# TSOC_USBUART2_R4_0.net
KiCad netlist of a schematic drawn in EAGLE
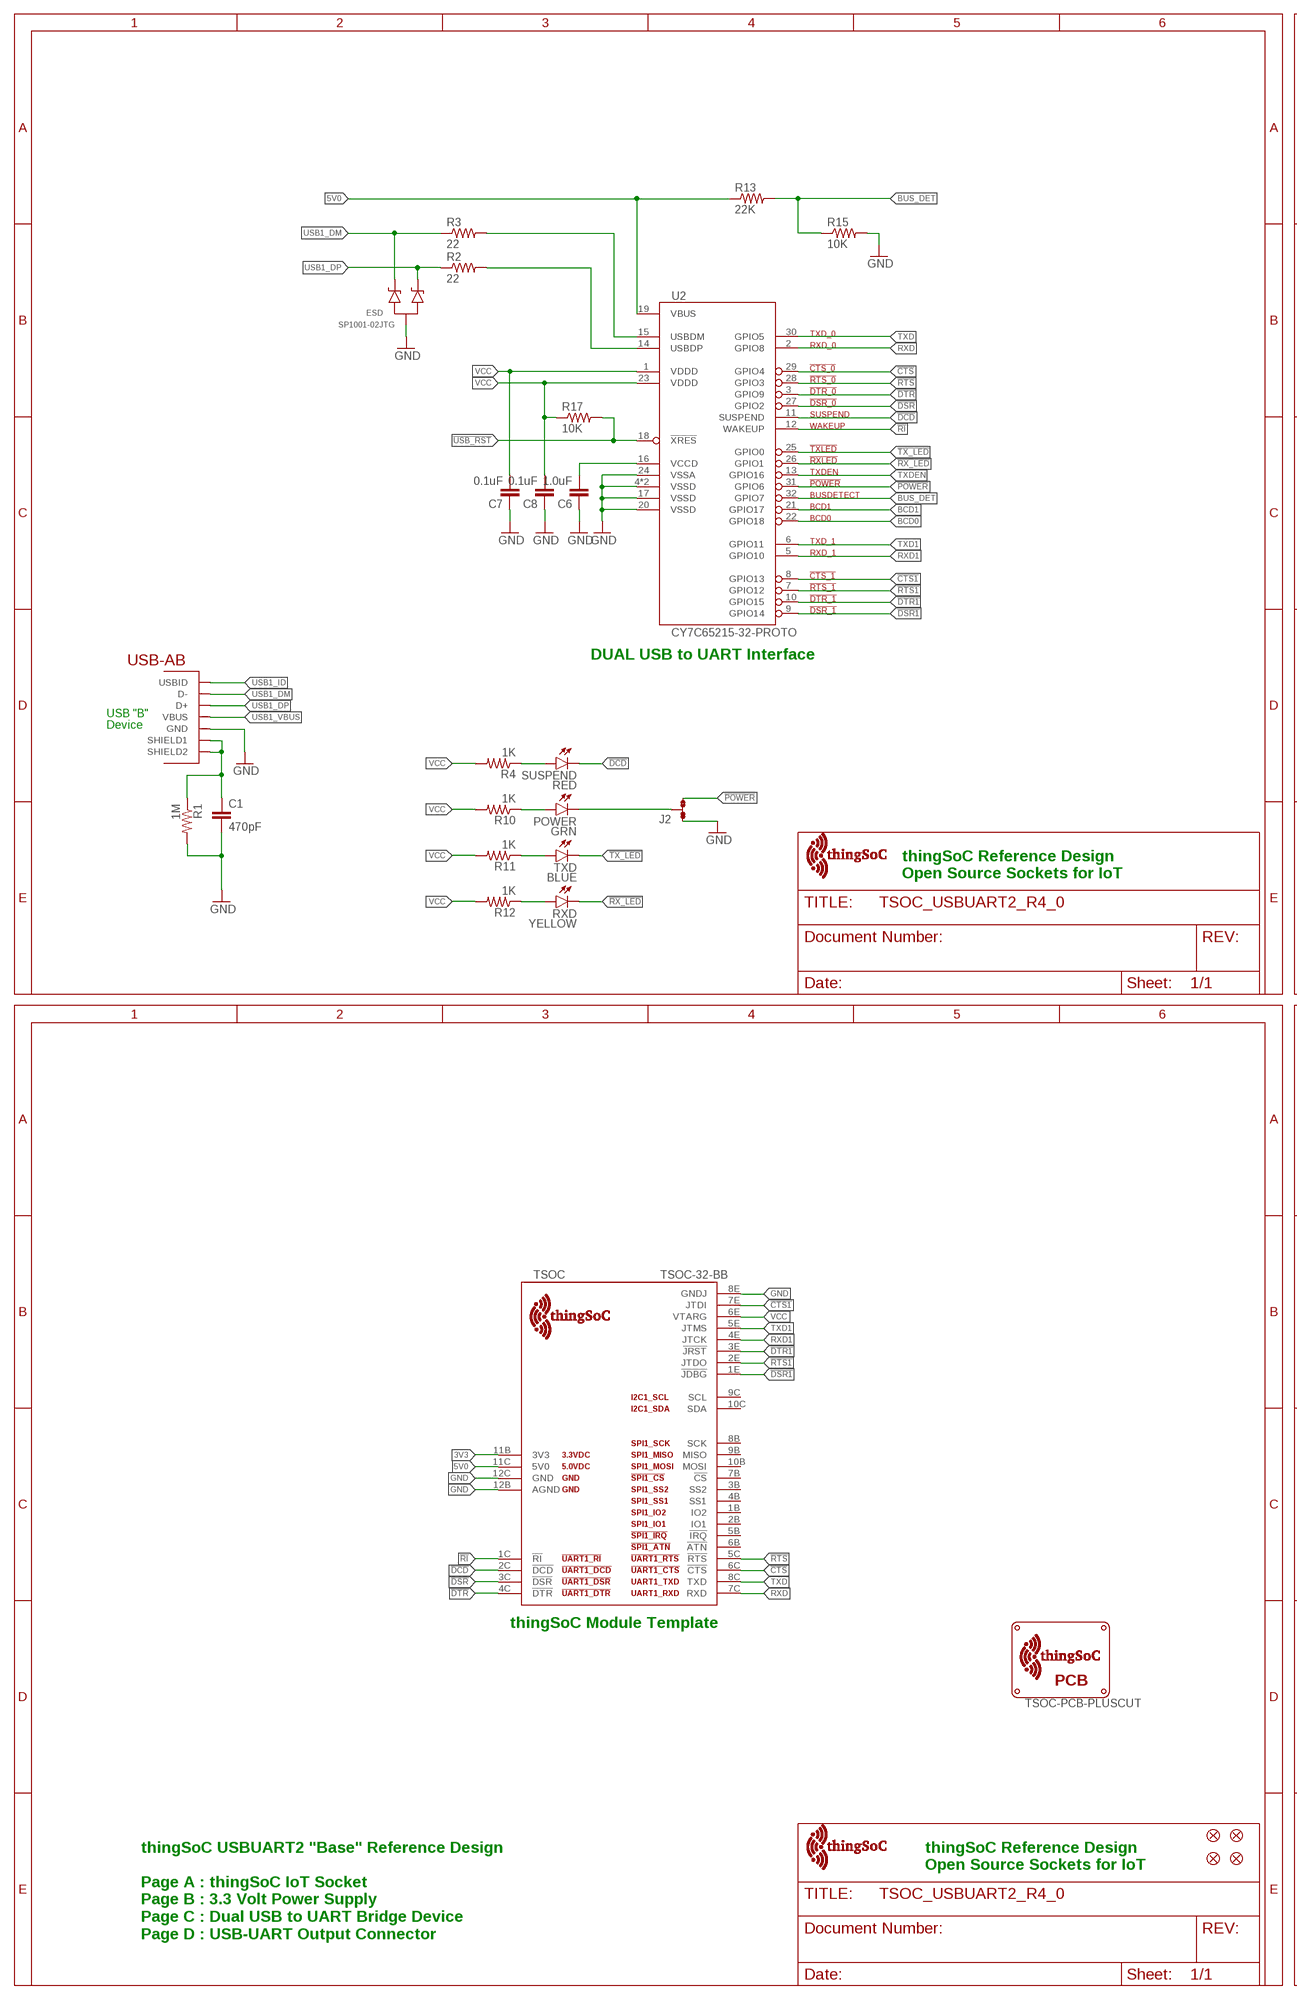
[diagram p0: schematic, sheet 1, part 1 of 2]
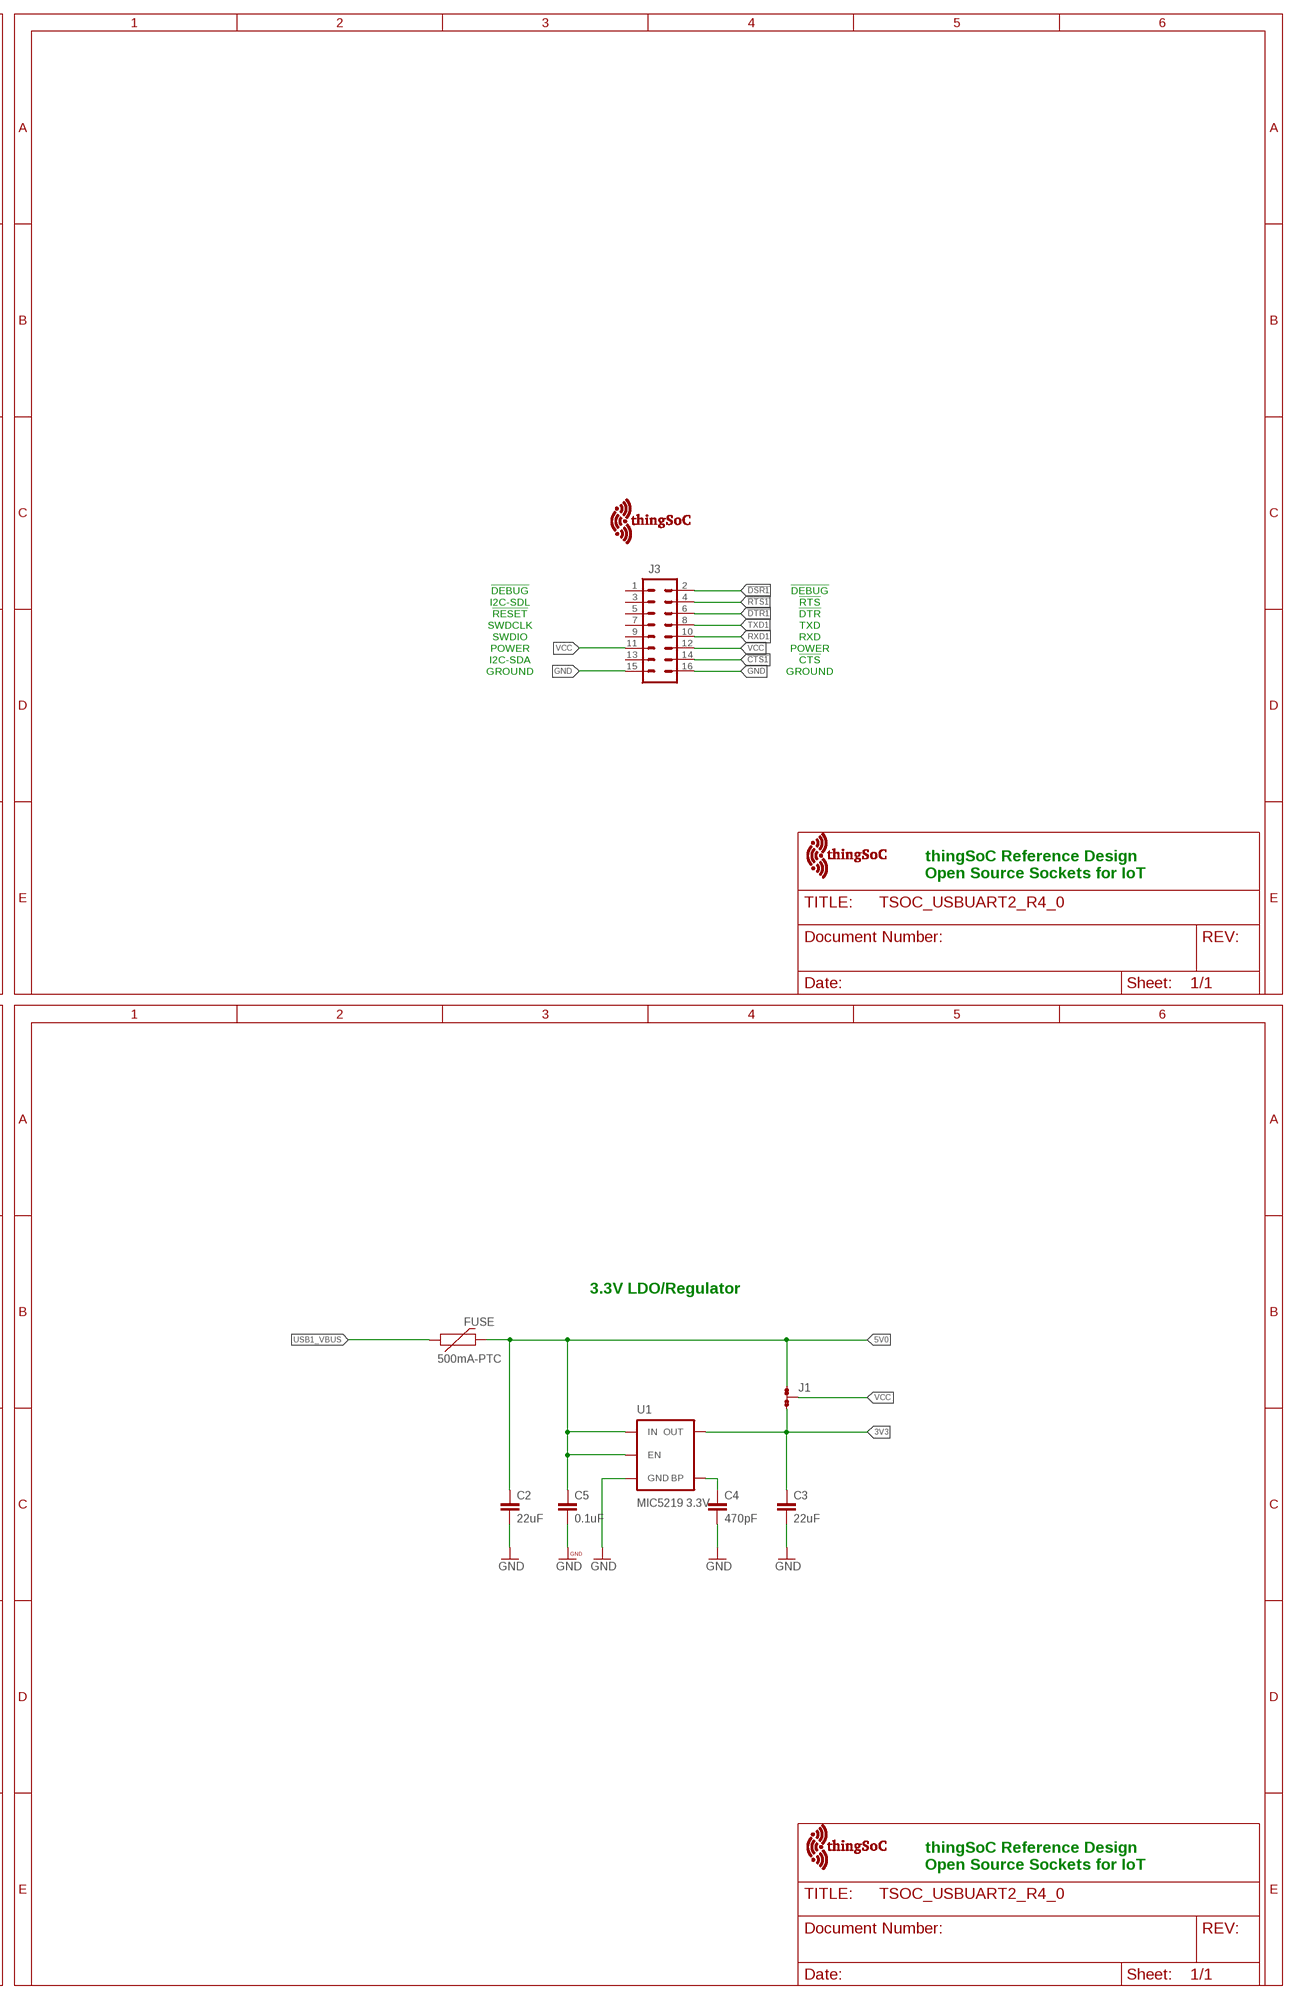
[diagram p1: schematic, sheet 1, part 2 of 2]

(export (version "E")
  (design (tool "Eeschema 10.0.6"))
  (components
    (comp (ref "C1")
      (value "470pF")
      (footprint "eagle-import:EIA-0603")
      (libsource (lib "eagle-import") (part "CAP-0603"))
    )
    (comp (ref "C2")
      (value "22uF")
      (footprint "eagle-import:EIA-1206")
      (libsource (lib "eagle-import") (part "CAP-1206"))
    )
    (comp (ref "C3")
      (value "22uF")
      (footprint "eagle-import:EIA-1206")
      (libsource (lib "eagle-import") (part "CAP-1206"))
    )
    (comp (ref "C4")
      (value "470pF")
      (footprint "eagle-import:EIA-0603")
      (libsource (lib "eagle-import") (part "CAP-0603"))
    )
    (comp (ref "C5")
      (value "0.1uF")
      (footprint "eagle-import:EIA-0603")
      (libsource (lib "eagle-import") (part "CAP-0603"))
    )
    (comp (ref "C6")
      (value "1.0uF")
      (footprint "eagle-import:EIA-0603")
      (libsource (lib "eagle-import") (part "CAP-0603"))
    )
    (comp (ref "C7")
      (value "0.1uF")
      (footprint "eagle-import:EIA-0603")
      (libsource (lib "eagle-import") (part "CAP-0603"))
    )
    (comp (ref "C8")
      (value "0.1uF")
      (footprint "eagle-import:EIA-0603")
      (libsource (lib "eagle-import") (part "CAP-0603"))
    )
    (comp (ref "ESD")
      (value "SP1001-02JTG")
      (footprint "eagle-import:SC70-3")
      (libsource (lib "eagle-import") (part "SP1001-02JTG"))
    )
    (comp (ref "FID1")
      (value "FIDUCIALUFIDUCIAL")
      (footprint "eagle-import:MICRO-FIDUCIAL")
      (libsource (lib "eagle-import") (part "FIDUCIALUFIDUCIAL"))
    )
    (comp (ref "FID2")
      (value "FIDUCIALUFIDUCIAL")
      (footprint "eagle-import:MICRO-FIDUCIAL")
      (libsource (lib "eagle-import") (part "FIDUCIALUFIDUCIAL"))
    )
    (comp (ref "FID3")
      (value "FIDUCIALUFIDUCIAL")
      (footprint "eagle-import:MICRO-FIDUCIAL")
      (libsource (lib "eagle-import") (part "FIDUCIALUFIDUCIAL"))
    )
    (comp (ref "FID4")
      (value "FIDUCIALUFIDUCIAL")
      (footprint "eagle-import:MICRO-FIDUCIAL")
      (libsource (lib "eagle-import") (part "FIDUCIALUFIDUCIAL"))
    )
    (comp (ref "FUSE")
      (value "500mA-PTC")
      (footprint "eagle-import:PTC-1206")
      (libsource (lib "eagle-import") (part "PTCSMD"))
    )
    (comp (ref "J1")
      (value "JMP-3-1_2")
      (footprint "eagle-import:JMP-3-1_2")
      (libsource (lib "eagle-import") (part "JMP-3-1_2"))
    )
    (comp (ref "J2")
      (value "JMP-3-1_2")
      (footprint "eagle-import:JMP-3-1_2")
      (libsource (lib "eagle-import") (part "JMP-3-1_2"))
    )
    (comp (ref "J3")
      (value "M08X2")
      (footprint "eagle-import:2X8")
      (libsource (lib "eagle-import") (part "M08X2"))
    )
    (comp (ref "POWER")
      (value "GRN")
      (footprint "eagle-import:LED-0603")
      (libsource (lib "eagle-import") (part "LED0603"))
    )
    (comp (ref "R1")
      (value "1M")
      (footprint "eagle-import:EIA-0603")
      (libsource (lib "eagle-import") (part "RESISTOR-0603"))
    )
    (comp (ref "R2")
      (value "22")
      (footprint "eagle-import:EIA-0603")
      (libsource (lib "eagle-import") (part "RESISTOR-0603"))
    )
    (comp (ref "R3")
      (value "22")
      (footprint "eagle-import:EIA-0603")
      (libsource (lib "eagle-import") (part "RESISTOR-0603"))
    )
    (comp (ref "R4")
      (value "1K")
      (footprint "eagle-import:EIA-0603")
      (libsource (lib "eagle-import") (part "RESISTOR-0603"))
    )
    (comp (ref "R10")
      (value "1K")
      (footprint "eagle-import:EIA-0603")
      (libsource (lib "eagle-import") (part "RESISTOR-0603"))
    )
    (comp (ref "R11")
      (value "1K")
      (footprint "eagle-import:EIA-0603")
      (libsource (lib "eagle-import") (part "RESISTOR-0603"))
    )
    (comp (ref "R12")
      (value "1K")
      (footprint "eagle-import:EIA-0603")
      (libsource (lib "eagle-import") (part "RESISTOR-0603"))
    )
    (comp (ref "R13")
      (value "22K")
      (footprint "eagle-import:EIA-0603")
      (libsource (lib "eagle-import") (part "RESISTOR-0603"))
    )
    (comp (ref "R15")
      (value "10K")
      (footprint "eagle-import:EIA-0603")
      (libsource (lib "eagle-import") (part "RESISTOR-0603"))
    )
    (comp (ref "R17")
      (value "10K")
      (footprint "eagle-import:EIA-0603")
      (libsource (lib "eagle-import") (part "RESISTOR-0603"))
    )
    (comp (ref "RXD")
      (value "YELLOW")
      (footprint "eagle-import:LED-0603")
      (libsource (lib "eagle-import") (part "LED0603"))
    )
    (comp (ref "SUSPEND")
      (value "RED")
      (footprint "eagle-import:LED-0603")
      (libsource (lib "eagle-import") (part "LED0603"))
    )
    (comp (ref "TSOC")
      (value "TSOC-32-BB")
      (footprint "eagle-import:TSOC-BB-S32")
      (libsource (lib "eagle-import") (part "TSOC-32-BB"))
    )
    (comp (ref "TXD")
      (value "BLUE")
      (footprint "eagle-import:LED-0603")
      (libsource (lib "eagle-import") (part "LED0603"))
    )
    (comp (ref "U$3")
      (value "TSOC-LOGO-LRG")
      (footprint "eagle-import:TSOC-LOGO-LRG")
      (libsource (lib "eagle-import") (part "TSOC-LOGO-LRG"))
    )
    (comp (ref "U$4")
      (value "TSOC-LOGO")
      (footprint "eagle-import:TSOC-LOGO-BLANK")
      (libsource (lib "eagle-import") (part "TSOC-LOGO"))
    )
    (comp (ref "U$5")
      (value "TSOC-LOGO")
      (footprint "eagle-import:TSOC-LOGO-BLANK")
      (libsource (lib "eagle-import") (part "TSOC-LOGO"))
    )
    (comp (ref "U$6")
      (value "TSOC-LOGO")
      (footprint "eagle-import:TSOC-LOGO-BLANK")
      (libsource (lib "eagle-import") (part "TSOC-LOGO"))
    )
    (comp (ref "U$7")
      (value "TSOC-PCB-PLUSCUT")
      (footprint "eagle-import:TSOC-BB-BRD-PLUS-CUT")
      (libsource (lib "eagle-import") (part "TSOC-PCB-PLUSCUT"))
    )
    (comp (ref "U$8")
      (value "TSOC-LOGO-SMALL")
      (footprint "eagle-import:TSOC-LOGO-SML")
      (libsource (lib "eagle-import") (part "TSOC-LOGO-SMALL"))
    )
    (comp (ref "U1")
      (value "MIC5219 3.3V")
      (footprint "eagle-import:SOT23-5")
      (libsource (lib "eagle-import") (part "V_REG_MIC52193.3V"))
    )
    (comp (ref "U2")
      (value "CY7C65215-32-PROTO")
      (footprint "eagle-import:QFN32-PROTO")
      (libsource (lib "eagle-import") (part "CY7C65215-32-PROTO"))
    )
    (comp (ref "USB")
      (value "USB_AB")
      (footprint "eagle-import:USB-AB-MICRO-SMD")
      (libsource (lib "eagle-import") (part "USB_AB"))
    )
  )
  (nets
    (net (code "1") (name "/~{CTS1}") (class "Default")
      (node (ref "J3") (pin "14") (pinfunction "14_14") (pintype "passive"))
      (node (ref "TSOC") (pin "7E") (pinfunction "JTDI_7E") (pintype "bidirectional"))
      (node (ref "U2") (pin "8") (pinfunction "GPIO13_8") (pintype "input"))
    )
    (net (code "2") (name "/~{CTS}") (class "Default")
      (node (ref "TSOC") (pin "6C") (pinfunction "~{CTS}_6C") (pintype "bidirectional"))
      (node (ref "U2") (pin "29") (pinfunction "GPIO4_29") (pintype "input"))
    )
    (net (code "3") (name "/~{DCD}") (class "Default")
      (node (ref "SUSPEND") (pin "C") (pinfunction "C_C") (pintype "passive"))
      (node (ref "TSOC") (pin "2C") (pinfunction "~{DCD}_2C") (pintype "bidirectional"))
      (node (ref "U2") (pin "11") (pinfunction "SUSPEND_11") (pintype "input"))
    )
    (net (code "4") (name "/~{DSR1}") (class "Default")
      (node (ref "J3") (pin "2") (pinfunction "2_2") (pintype "passive"))
      (node (ref "TSOC") (pin "1E") (pinfunction "~{JDBG}_1E") (pintype "bidirectional"))
      (node (ref "U2") (pin "9") (pinfunction "GPIO14_9") (pintype "input"))
    )
    (net (code "5") (name "/~{DSR}") (class "Default")
      (node (ref "TSOC") (pin "3C") (pinfunction "~{DSR}_3C") (pintype "bidirectional"))
      (node (ref "U2") (pin "27") (pinfunction "GPIO2_27") (pintype "input"))
    )
    (net (code "6") (name "/~{DTR1}") (class "Default")
      (node (ref "J3") (pin "6") (pinfunction "6_6") (pintype "passive"))
      (node (ref "TSOC") (pin "3E") (pinfunction "~{JRST}_3E") (pintype "bidirectional"))
      (node (ref "U2") (pin "10") (pinfunction "GPIO15_10") (pintype "output"))
    )
    (net (code "7") (name "/~{DTR}") (class "Default")
      (node (ref "TSOC") (pin "4C") (pinfunction "~{DTR}_4C") (pintype "bidirectional"))
      (node (ref "U2") (pin "3") (pinfunction "GPIO9_3") (pintype "output"))
    )
    (net (code "8") (name "/~{POWER}") (class "Default")
      (node (ref "J2") (pin "3") (pinfunction "3_3") (pintype "passive"))
      (node (ref "U2") (pin "31") (pinfunction "GPIO6_31") (pintype "input"))
    )
    (net (code "9") (name "/~{RI}") (class "Default")
      (node (ref "TSOC") (pin "1C") (pinfunction "~{RI}_1C") (pintype "bidirectional"))
      (node (ref "U2") (pin "12") (pinfunction "WAKEUP_12") (pintype "input"))
    )
    (net (code "10") (name "/~{RTS1}") (class "Default")
      (node (ref "J3") (pin "4") (pinfunction "4_4") (pintype "passive"))
      (node (ref "TSOC") (pin "2E") (pinfunction "JTDO_2E") (pintype "bidirectional"))
      (node (ref "U2") (pin "7") (pinfunction "GPIO12_7") (pintype "output"))
    )
    (net (code "11") (name "/~{RTS}") (class "Default")
      (node (ref "TSOC") (pin "5C") (pinfunction "~{RTS}_5C") (pintype "bidirectional"))
      (node (ref "U2") (pin "28") (pinfunction "GPIO3_28") (pintype "output"))
    )
    (net (code "12") (name "/~{RX_LED}") (class "Default")
      (node (ref "RXD") (pin "C") (pinfunction "C_C") (pintype "passive"))
      (node (ref "U2") (pin "26") (pinfunction "GPIO1_26") (pintype "input"))
    )
    (net (code "13") (name "/~{TX_LED}") (class "Default")
      (node (ref "TXD") (pin "C") (pinfunction "C_C") (pintype "passive"))
      (node (ref "U2") (pin "25") (pinfunction "GPIO0_25") (pintype "input"))
    )
    (net (code "14") (name "/~{USB_RST}") (class "Default")
      (node (ref "R17") (pin "2") (pinfunction "2_2") (pintype "passive"))
      (node (ref "U2") (pin "18") (pinfunction "~{XRES}_18") (pintype "input"))
    )
    (net (code "15") (name "3V3") (class "Default")
      (node (ref "C3") (pin "1") (pinfunction "1_1") (pintype "passive"))
      (node (ref "J1") (pin "3") (pinfunction "3_3") (pintype "passive"))
      (node (ref "TSOC") (pin "11B") (pinfunction "3V3_11B") (pintype "bidirectional"))
      (node (ref "U1") (pin "5") (pinfunction "OUT_5") (pintype "passive"))
    )
    (net (code "16") (name "5V0") (class "Default")
      (node (ref "C2") (pin "1") (pinfunction "1_1") (pintype "passive"))
      (node (ref "C5") (pin "1") (pinfunction "1_1") (pintype "passive"))
      (node (ref "FUSE") (pin "2") (pinfunction "2_2") (pintype "bidirectional"))
      (node (ref "J1") (pin "1") (pinfunction "1_1") (pintype "passive"))
      (node (ref "R13") (pin "1") (pinfunction "1_1") (pintype "passive"))
      (node (ref "TSOC") (pin "11C") (pinfunction "5V0_11C") (pintype "bidirectional"))
      (node (ref "U1") (pin "1") (pinfunction "IN_1") (pintype "input"))
      (node (ref "U1") (pin "3") (pinfunction "EN_3") (pintype "input"))
      (node (ref "U2") (pin "19") (pinfunction "VBUS_19") (pintype "power_in"))
    )
    (net (code "17") (name "BCD0") (class "Default")
      (node (ref "U2") (pin "22") (pinfunction "GPIO18_22") (pintype "input"))
    )
    (net (code "18") (name "BCD1") (class "Default")
      (node (ref "U2") (pin "21") (pinfunction "GPIO17_21") (pintype "input"))
    )
    (net (code "19") (name "BUS_DET") (class "Default")
      (node (ref "R13") (pin "2") (pinfunction "2_2") (pintype "passive"))
      (node (ref "R15") (pin "1") (pinfunction "1_1") (pintype "passive"))
      (node (ref "U2") (pin "32") (pinfunction "GPIO7_32") (pintype "input"))
    )
    (net (code "20") (name "GND") (class "Default")
      (node (ref "C1") (pin "2") (pinfunction "2_2") (pintype "passive"))
      (node (ref "C2") (pin "2") (pinfunction "2_2") (pintype "passive"))
      (node (ref "C3") (pin "2") (pinfunction "2_2") (pintype "passive"))
      (node (ref "C4") (pin "2") (pinfunction "2_2") (pintype "passive"))
      (node (ref "C5") (pin "2") (pinfunction "2_2") (pintype "passive"))
      (node (ref "C6") (pin "1") (pinfunction "1_1") (pintype "passive"))
      (node (ref "C7") (pin "1") (pinfunction "1_1") (pintype "passive"))
      (node (ref "C8") (pin "1") (pinfunction "1_1") (pintype "passive"))
      (node (ref "ESD") (pin "3") (pinfunction "A_3") (pintype "passive"))
      (node (ref "J2") (pin "1") (pinfunction "1_1") (pintype "passive"))
      (node (ref "J3") (pin "15") (pinfunction "15_15") (pintype "passive"))
      (node (ref "J3") (pin "16") (pinfunction "16_16") (pintype "passive"))
      (node (ref "R1") (pin "2") (pinfunction "2_2") (pintype "passive"))
      (node (ref "R15") (pin "2") (pinfunction "2_2") (pintype "passive"))
      (node (ref "TSOC") (pin "12B") (pinfunction "AGND_12B") (pintype "bidirectional"))
      (node (ref "TSOC") (pin "12C") (pinfunction "GND_12C") (pintype "bidirectional"))
      (node (ref "TSOC") (pin "8E") (pinfunction "GNDJ_8E") (pintype "bidirectional"))
      (node (ref "U1") (pin "2") (pinfunction "GND_2") (pintype "input"))
      (node (ref "U2") (pin "17") (pinfunction "VSSD_17") (pintype "power_in"))
      (node (ref "U2") (pin "20") (pinfunction "VSSD_20") (pintype "power_in"))
      (node (ref "U2") (pin "24") (pinfunction "VSSA_24") (pintype "power_in"))
      (node (ref "U2") (pin "4") (pinfunction "VSSD_4") (pintype "power_in"))
      (node (ref "U2") (pin "EXP") (pinfunction "VSSD_EXP") (pintype "power_in"))
      (node (ref "USB") (pin "GND") (pinfunction "GND_GND") (pintype "bidirectional"))
    )
    (net (code "21") (name "Net-(C1-Pad1)") (class "Default")
      (node (ref "C1") (pin "1") (pinfunction "1_1") (pintype "passive"))
      (node (ref "R1") (pin "1") (pinfunction "1_1") (pintype "passive"))
      (node (ref "USB") (pin "SHIELD1") (pinfunction "SHIELD1_SHIELD1") (pintype "bidirectional"))
      (node (ref "USB") (pin "SHIELD2") (pinfunction "SHIELD2_SHIELD2") (pintype "bidirectional"))
    )
    (net (code "22") (name "Net-(J2-Pad2)") (class "Default")
      (node (ref "J2") (pin "2") (pinfunction "2_2") (pintype "passive"))
      (node (ref "POWER") (pin "C") (pinfunction "C_C") (pintype "passive"))
    )
    (net (code "23") (name "Net-(POWER-PadA)") (class "Default")
      (node (ref "POWER") (pin "A") (pinfunction "A_A") (pintype "passive"))
      (node (ref "R10") (pin "1") (pinfunction "1_1") (pintype "passive"))
    )
    (net (code "24") (name "Net-(R4-Pad1)") (class "Default")
      (node (ref "R4") (pin "1") (pinfunction "1_1") (pintype "passive"))
      (node (ref "SUSPEND") (pin "A") (pinfunction "A_A") (pintype "passive"))
    )
    (net (code "25") (name "Net-(R11-Pad1)") (class "Default")
      (node (ref "R11") (pin "1") (pinfunction "1_1") (pintype "passive"))
      (node (ref "TXD") (pin "A") (pinfunction "A_A") (pintype "passive"))
    )
    (net (code "26") (name "Net-(R12-Pad1)") (class "Default")
      (node (ref "R12") (pin "1") (pinfunction "1_1") (pintype "passive"))
      (node (ref "RXD") (pin "A") (pinfunction "A_A") (pintype "passive"))
    )
    (net (code "27") (name "Net-(U1-BP)") (class "Default")
      (node (ref "C4") (pin "1") (pinfunction "1_1") (pintype "passive"))
      (node (ref "U1") (pin "4") (pinfunction "BP_4") (pintype "input"))
    )
    (net (code "28") (name "Net-(U2-USBDM)") (class "Default")
      (node (ref "R3") (pin "2") (pinfunction "2_2") (pintype "passive"))
      (node (ref "U2") (pin "15") (pinfunction "USBDM_15") (pintype "bidirectional"))
    )
    (net (code "29") (name "Net-(U2-USBDP)") (class "Default")
      (node (ref "R2") (pin "2") (pinfunction "2_2") (pintype "passive"))
      (node (ref "U2") (pin "14") (pinfunction "USBDP_14") (pintype "bidirectional"))
    )
    (net (code "30") (name "Net-(U2-VCCD)") (class "Default")
      (node (ref "C6") (pin "2") (pinfunction "2_2") (pintype "passive"))
      (node (ref "U2") (pin "16") (pinfunction "VCCD_16") (pintype "output"))
    )
    (net (code "31") (name "RXD") (class "Default")
      (node (ref "TSOC") (pin "7C") (pinfunction "RXD_7C") (pintype "bidirectional"))
      (node (ref "U2") (pin "2") (pinfunction "GPIO8_2") (pintype "input"))
    )
    (net (code "32") (name "RXD1") (class "Default")
      (node (ref "J3") (pin "10") (pinfunction "10_10") (pintype "passive"))
      (node (ref "TSOC") (pin "4E") (pinfunction "JTCK_4E") (pintype "bidirectional"))
      (node (ref "U2") (pin "5") (pinfunction "GPIO10_5") (pintype "input"))
    )
    (net (code "33") (name "TXD") (class "Default")
      (node (ref "TSOC") (pin "8C") (pinfunction "TXD_8C") (pintype "bidirectional"))
      (node (ref "U2") (pin "30") (pinfunction "GPIO5_30") (pintype "output"))
    )
    (net (code "34") (name "TXD1") (class "Default")
      (node (ref "J3") (pin "8") (pinfunction "8_8") (pintype "passive"))
      (node (ref "TSOC") (pin "5E") (pinfunction "JTMS_5E") (pintype "bidirectional"))
      (node (ref "U2") (pin "6") (pinfunction "GPIO11_6") (pintype "output"))
    )
    (net (code "35") (name "TXDEN") (class "Default")
      (node (ref "U2") (pin "13") (pinfunction "GPIO16_13") (pintype "output"))
    )
    (net (code "36") (name "USB1_DM") (class "Default")
      (node (ref "ESD") (pin "2") (pinfunction "C2_2") (pintype "passive"))
      (node (ref "R3") (pin "1") (pinfunction "1_1") (pintype "passive"))
      (node (ref "USB") (pin "D-") (pinfunction "D-_D-") (pintype "bidirectional"))
    )
    (net (code "37") (name "USB1_DP") (class "Default")
      (node (ref "ESD") (pin "1") (pinfunction "C1_1") (pintype "passive"))
      (node (ref "R2") (pin "1") (pinfunction "1_1") (pintype "passive"))
      (node (ref "USB") (pin "D+") (pinfunction "D+_D+") (pintype "bidirectional"))
    )
    (net (code "38") (name "USB1_ID") (class "Default")
      (node (ref "USB") (pin "ID") (pinfunction "USBID_ID") (pintype "bidirectional"))
    )
    (net (code "39") (name "USB1_VBUS") (class "Default")
      (node (ref "FUSE") (pin "1") (pinfunction "1_1") (pintype "bidirectional"))
      (node (ref "USB") (pin "VBUS") (pinfunction "VBUS_VBUS") (pintype "bidirectional"))
    )
    (net (code "40") (name "VCC") (class "Default")
      (node (ref "C7") (pin "2") (pinfunction "2_2") (pintype "passive"))
      (node (ref "C8") (pin "2") (pinfunction "2_2") (pintype "passive"))
      (node (ref "J1") (pin "2") (pinfunction "2_2") (pintype "passive"))
      (node (ref "J3") (pin "11") (pinfunction "11_11") (pintype "passive"))
      (node (ref "J3") (pin "12") (pinfunction "12_12") (pintype "passive"))
      (node (ref "R10") (pin "2") (pinfunction "2_2") (pintype "passive"))
      (node (ref "R11") (pin "2") (pinfunction "2_2") (pintype "passive"))
      (node (ref "R12") (pin "2") (pinfunction "2_2") (pintype "passive"))
      (node (ref "R17") (pin "1") (pinfunction "1_1") (pintype "passive"))
      (node (ref "R4") (pin "2") (pinfunction "2_2") (pintype "passive"))
      (node (ref "TSOC") (pin "6E") (pinfunction "VTARG_6E") (pintype "bidirectional"))
      (node (ref "U2") (pin "1") (pinfunction "VDDD_1") (pintype "power_in"))
      (node (ref "U2") (pin "23") (pinfunction "VDDD_23") (pintype "power_in"))
    )
    (net (code "41") (name "unconnected-(J3-Pad1)") (class "Default")
      (node (ref "J3") (pin "1") (pinfunction "1_1") (pintype "passive"))
    )
    (net (code "42") (name "unconnected-(J3-Pad3)") (class "Default")
      (node (ref "J3") (pin "3") (pinfunction "3_3") (pintype "passive"))
    )
    (net (code "43") (name "unconnected-(J3-Pad5)") (class "Default")
      (node (ref "J3") (pin "5") (pinfunction "5_5") (pintype "passive"))
    )
    (net (code "44") (name "unconnected-(J3-Pad7)") (class "Default")
      (node (ref "J3") (pin "7") (pinfunction "7_7") (pintype "passive"))
    )
    (net (code "45") (name "unconnected-(J3-Pad9)") (class "Default")
      (node (ref "J3") (pin "9") (pinfunction "9_9") (pintype "passive"))
    )
    (net (code "46") (name "unconnected-(J3-Pad13)") (class "Default")
      (node (ref "J3") (pin "13") (pinfunction "13_13") (pintype "passive"))
    )
    (net (code "47") (name "unconnected-(TSOC-IO1-Pad2B)") (class "Default")
      (node (ref "TSOC") (pin "2B") (pinfunction "IO1_2B") (pintype "bidirectional"))
    )
    (net (code "48") (name "unconnected-(TSOC-IO2-Pad1B)") (class "Default")
      (node (ref "TSOC") (pin "1B") (pinfunction "IO2_1B") (pintype "bidirectional"))
    )
    (net (code "49") (name "unconnected-(TSOC-MISO-Pad9B)") (class "Default")
      (node (ref "TSOC") (pin "9B") (pinfunction "MISO_9B") (pintype "bidirectional"))
    )
    (net (code "50") (name "unconnected-(TSOC-MOSI-Pad10B)") (class "Default")
      (node (ref "TSOC") (pin "10B") (pinfunction "MOSI_10B") (pintype "bidirectional"))
    )
    (net (code "51") (name "unconnected-(TSOC-SCK-Pad8B)") (class "Default")
      (node (ref "TSOC") (pin "8B") (pinfunction "SCK_8B") (pintype "bidirectional"))
    )
    (net (code "52") (name "unconnected-(TSOC-SCL-Pad9C)") (class "Default")
      (node (ref "TSOC") (pin "9C") (pinfunction "SCL_9C") (pintype "bidirectional"))
    )
    (net (code "53") (name "unconnected-(TSOC-SDA-Pad10C)") (class "Default")
      (node (ref "TSOC") (pin "10C") (pinfunction "SDA_10C") (pintype "bidirectional"))
    )
    (net (code "54") (name "unconnected-(TSOC-SS1-Pad4B)") (class "Default")
      (node (ref "TSOC") (pin "4B") (pinfunction "SS1_4B") (pintype "bidirectional"))
    )
    (net (code "55") (name "unconnected-(TSOC-SS2-Pad3B)") (class "Default")
      (node (ref "TSOC") (pin "3B") (pinfunction "SS2_3B") (pintype "bidirectional"))
    )
    (net (code "56") (name "unconnected-(TSOC-~{ATN}-Pad6B)") (class "Default")
      (node (ref "TSOC") (pin "6B") (pinfunction "~{ATN}_6B") (pintype "bidirectional"))
    )
    (net (code "57") (name "unconnected-(TSOC-~{CS}-Pad7B)") (class "Default")
      (node (ref "TSOC") (pin "7B") (pinfunction "~{CS}_7B") (pintype "bidirectional"))
    )
    (net (code "58") (name "unconnected-(TSOC-~{IRQ}-Pad5B)") (class "Default")
      (node (ref "TSOC") (pin "5B") (pinfunction "~{IRQ}_5B") (pintype "bidirectional"))
    )
  )
)
